# ai_breakout_rpibplus.net
KiCad netlist of a schematic drawn in EAGLE
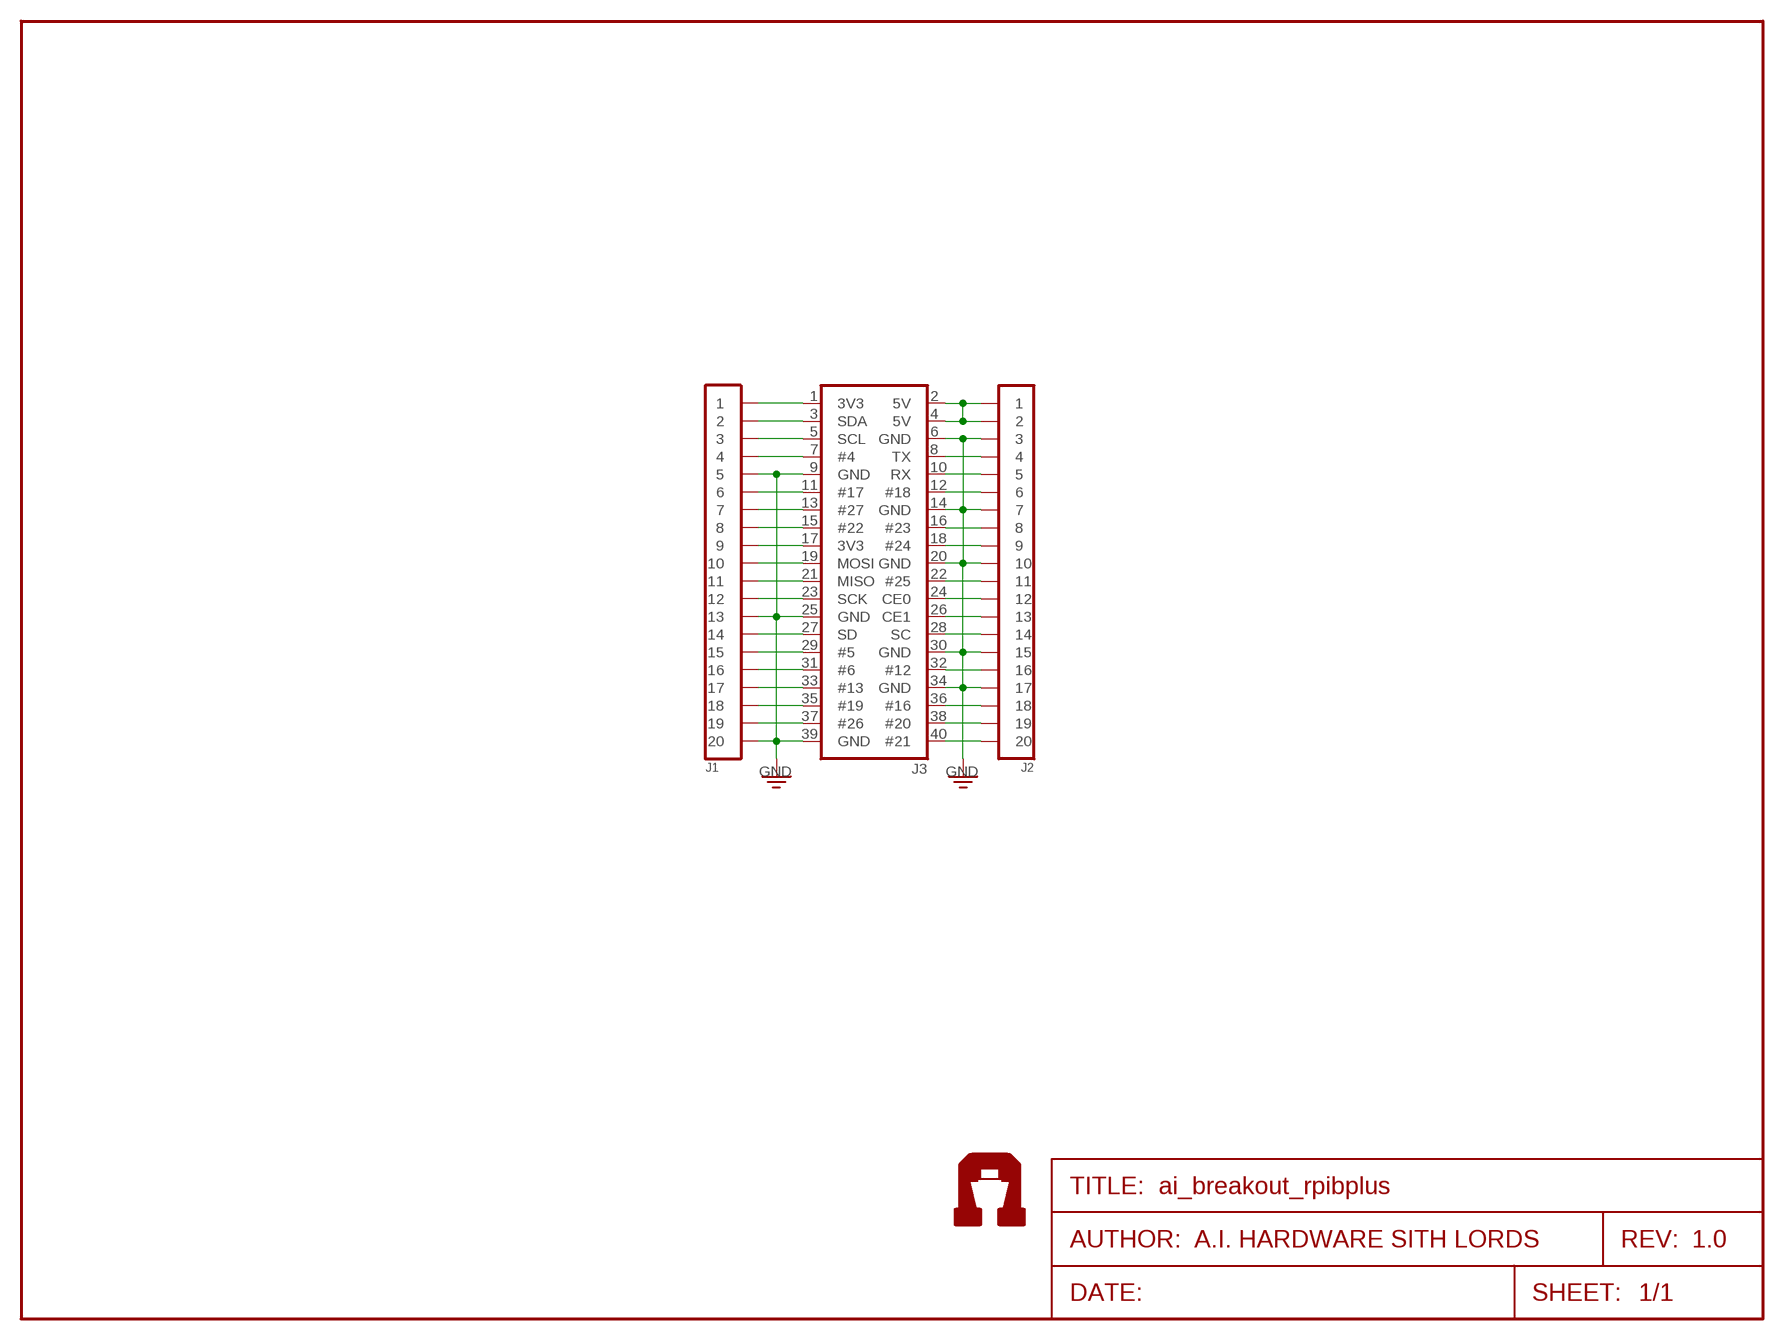
[diagram p0: schematic, sheet 1]

(export (version "E")
  (design (tool "Eeschema 10.0.6"))
  (components
    (comp (ref "J1")
      (value "1X20")
      (footprint "eagle-import:1X20")
      (libsource (lib "eagle-import") (part "1X20"))
    )
    (comp (ref "J2")
      (value "1X20NOFIRST")
      (footprint "eagle-import:1X20-NOFIRST")
      (libsource (lib "eagle-import") (part "1X20NOFIRST"))
    )
    (comp (ref "J3")
      (value "2X20-RPI-BRK")
      (footprint "eagle-import:2X20-RPI-BRK")
      (libsource (lib "eagle-import") (part "2X20-RPI-BRK"))
    )
    (comp (ref "U$1")
      (value "AI-LOGOXS")
      (footprint "eagle-import:AI-LOGO-XS")
      (libsource (lib "eagle-import") (part "AI-LOGOXS"))
    )
    (comp (ref "U$2")
      (value "AI-LOGOXS")
      (footprint "eagle-import:AI-LOGO-XS")
      (libsource (lib "eagle-import") (part "AI-LOGOXS"))
    )
  )
  (nets
    (net (code "1") (name "GND") (class "Default")
      (node (ref "J1") (pin "13") (pinfunction "13_13") (pintype "bidirectional"))
      (node (ref "J1") (pin "20") (pinfunction "20_20") (pintype "bidirectional"))
      (node (ref "J1") (pin "5") (pinfunction "5_5") (pintype "bidirectional"))
      (node (ref "J2") (pin "10") (pinfunction "10_10") (pintype "bidirectional"))
      (node (ref "J2") (pin "15") (pinfunction "15_15") (pintype "bidirectional"))
      (node (ref "J2") (pin "17") (pinfunction "17_17") (pintype "bidirectional"))
      (node (ref "J2") (pin "3") (pinfunction "3_3") (pintype "bidirectional"))
      (node (ref "J2") (pin "7") (pinfunction "7_7") (pintype "bidirectional"))
      (node (ref "J3") (pin "14") (pinfunction "GND_14") (pintype "bidirectional"))
      (node (ref "J3") (pin "20") (pinfunction "GND_20") (pintype "bidirectional"))
      (node (ref "J3") (pin "25") (pinfunction "GND_25") (pintype "bidirectional"))
      (node (ref "J3") (pin "30") (pinfunction "GND_30") (pintype "bidirectional"))
      (node (ref "J3") (pin "34") (pinfunction "GND_34") (pintype "bidirectional"))
      (node (ref "J3") (pin "39") (pinfunction "GND_39") (pintype "bidirectional"))
      (node (ref "J3") (pin "6") (pinfunction "GND_6") (pintype "bidirectional"))
      (node (ref "J3") (pin "9") (pinfunction "GND_9") (pintype "bidirectional"))
    )
    (net (code "2") (name "Net-(J1-Pad1)") (class "Default")
      (node (ref "J1") (pin "1") (pinfunction "1_1") (pintype "bidirectional"))
      (node (ref "J3") (pin "1") (pinfunction "3V3_1") (pintype "bidirectional"))
    )
    (net (code "3") (name "Net-(J1-Pad9)") (class "Default")
      (node (ref "J1") (pin "9") (pinfunction "9_9") (pintype "bidirectional"))
      (node (ref "J3") (pin "17") (pinfunction "3V3_17") (pintype "bidirectional"))
    )
    (net (code "4") (name "Net-(J2-Pad1)") (class "Default")
      (node (ref "J2") (pin "1") (pinfunction "1_1") (pintype "bidirectional"))
      (node (ref "J2") (pin "2") (pinfunction "2_2") (pintype "bidirectional"))
      (node (ref "J3") (pin "2") (pinfunction "5V_2") (pintype "bidirectional"))
      (node (ref "J3") (pin "4") (pinfunction "5V_4") (pintype "bidirectional"))
    )
    (net (code "5") (name "Net-(J3-#4)") (class "Default")
      (node (ref "J1") (pin "4") (pinfunction "4_4") (pintype "bidirectional"))
      (node (ref "J3") (pin "7") (pinfunction "#4_7") (pintype "bidirectional"))
    )
    (net (code "6") (name "Net-(J3-#5)") (class "Default")
      (node (ref "J1") (pin "15") (pinfunction "15_15") (pintype "bidirectional"))
      (node (ref "J3") (pin "29") (pinfunction "#5_29") (pintype "bidirectional"))
    )
    (net (code "7") (name "Net-(J3-#6)") (class "Default")
      (node (ref "J1") (pin "16") (pinfunction "16_16") (pintype "bidirectional"))
      (node (ref "J3") (pin "31") (pinfunction "#6_31") (pintype "bidirectional"))
    )
    (net (code "8") (name "Net-(J3-#12)") (class "Default")
      (node (ref "J2") (pin "16") (pinfunction "16_16") (pintype "bidirectional"))
      (node (ref "J3") (pin "32") (pinfunction "#12_32") (pintype "bidirectional"))
    )
    (net (code "9") (name "Net-(J3-#13)") (class "Default")
      (node (ref "J1") (pin "17") (pinfunction "17_17") (pintype "bidirectional"))
      (node (ref "J3") (pin "33") (pinfunction "#13_33") (pintype "bidirectional"))
    )
    (net (code "10") (name "Net-(J3-#16)") (class "Default")
      (node (ref "J2") (pin "18") (pinfunction "18_18") (pintype "bidirectional"))
      (node (ref "J3") (pin "36") (pinfunction "#16_36") (pintype "bidirectional"))
    )
    (net (code "11") (name "Net-(J3-#17)") (class "Default")
      (node (ref "J1") (pin "6") (pinfunction "6_6") (pintype "bidirectional"))
      (node (ref "J3") (pin "11") (pinfunction "#17_11") (pintype "bidirectional"))
    )
    (net (code "12") (name "Net-(J3-#18)") (class "Default")
      (node (ref "J2") (pin "6") (pinfunction "6_6") (pintype "bidirectional"))
      (node (ref "J3") (pin "12") (pinfunction "#18_12") (pintype "bidirectional"))
    )
    (net (code "13") (name "Net-(J3-#19)") (class "Default")
      (node (ref "J1") (pin "18") (pinfunction "18_18") (pintype "bidirectional"))
      (node (ref "J3") (pin "35") (pinfunction "#19_35") (pintype "bidirectional"))
    )
    (net (code "14") (name "Net-(J3-#20)") (class "Default")
      (node (ref "J2") (pin "19") (pinfunction "19_19") (pintype "bidirectional"))
      (node (ref "J3") (pin "38") (pinfunction "#20_38") (pintype "bidirectional"))
    )
    (net (code "15") (name "Net-(J3-#21)") (class "Default")
      (node (ref "J2") (pin "20") (pinfunction "20_20") (pintype "bidirectional"))
      (node (ref "J3") (pin "40") (pinfunction "#21_40") (pintype "bidirectional"))
    )
    (net (code "16") (name "Net-(J3-#22)") (class "Default")
      (node (ref "J1") (pin "8") (pinfunction "8_8") (pintype "bidirectional"))
      (node (ref "J3") (pin "15") (pinfunction "#22_15") (pintype "bidirectional"))
    )
    (net (code "17") (name "Net-(J3-#23)") (class "Default")
      (node (ref "J2") (pin "8") (pinfunction "8_8") (pintype "bidirectional"))
      (node (ref "J3") (pin "16") (pinfunction "#23_16") (pintype "bidirectional"))
    )
    (net (code "18") (name "Net-(J3-#24)") (class "Default")
      (node (ref "J2") (pin "9") (pinfunction "9_9") (pintype "bidirectional"))
      (node (ref "J3") (pin "18") (pinfunction "#24_18") (pintype "bidirectional"))
    )
    (net (code "19") (name "Net-(J3-#25)") (class "Default")
      (node (ref "J2") (pin "11") (pinfunction "11_11") (pintype "bidirectional"))
      (node (ref "J3") (pin "22") (pinfunction "#25_22") (pintype "bidirectional"))
    )
    (net (code "20") (name "Net-(J3-#26)") (class "Default")
      (node (ref "J1") (pin "19") (pinfunction "19_19") (pintype "bidirectional"))
      (node (ref "J3") (pin "37") (pinfunction "#26_37") (pintype "bidirectional"))
    )
    (net (code "21") (name "Net-(J3-#27)") (class "Default")
      (node (ref "J1") (pin "7") (pinfunction "7_7") (pintype "bidirectional"))
      (node (ref "J3") (pin "13") (pinfunction "#27_13") (pintype "bidirectional"))
    )
    (net (code "22") (name "Net-(J3-CE0)") (class "Default")
      (node (ref "J2") (pin "12") (pinfunction "12_12") (pintype "bidirectional"))
      (node (ref "J3") (pin "24") (pinfunction "CE0_24") (pintype "bidirectional"))
    )
    (net (code "23") (name "Net-(J3-CE1)") (class "Default")
      (node (ref "J2") (pin "13") (pinfunction "13_13") (pintype "bidirectional"))
      (node (ref "J3") (pin "26") (pinfunction "CE1_26") (pintype "bidirectional"))
    )
    (net (code "24") (name "Net-(J3-MISO)") (class "Default")
      (node (ref "J1") (pin "11") (pinfunction "11_11") (pintype "bidirectional"))
      (node (ref "J3") (pin "21") (pinfunction "MISO_21") (pintype "bidirectional"))
    )
    (net (code "25") (name "Net-(J3-MOSI)") (class "Default")
      (node (ref "J1") (pin "10") (pinfunction "10_10") (pintype "bidirectional"))
      (node (ref "J3") (pin "19") (pinfunction "MOSI_19") (pintype "bidirectional"))
    )
    (net (code "26") (name "Net-(J3-RX)") (class "Default")
      (node (ref "J2") (pin "5") (pinfunction "5_5") (pintype "bidirectional"))
      (node (ref "J3") (pin "10") (pinfunction "RX_10") (pintype "bidirectional"))
    )
    (net (code "27") (name "Net-(J3-SC)") (class "Default")
      (node (ref "J2") (pin "14") (pinfunction "14_14") (pintype "bidirectional"))
      (node (ref "J3") (pin "28") (pinfunction "SC_28") (pintype "bidirectional"))
    )
    (net (code "28") (name "Net-(J3-SCK)") (class "Default")
      (node (ref "J1") (pin "12") (pinfunction "12_12") (pintype "bidirectional"))
      (node (ref "J3") (pin "23") (pinfunction "SCK_23") (pintype "bidirectional"))
    )
    (net (code "29") (name "Net-(J3-SCL)") (class "Default")
      (node (ref "J1") (pin "3") (pinfunction "3_3") (pintype "bidirectional"))
      (node (ref "J3") (pin "5") (pinfunction "SCL_5") (pintype "bidirectional"))
    )
    (net (code "30") (name "Net-(J3-SD)") (class "Default")
      (node (ref "J1") (pin "14") (pinfunction "14_14") (pintype "bidirectional"))
      (node (ref "J3") (pin "27") (pinfunction "SD_27") (pintype "bidirectional"))
    )
    (net (code "31") (name "Net-(J3-SDA)") (class "Default")
      (node (ref "J1") (pin "2") (pinfunction "2_2") (pintype "bidirectional"))
      (node (ref "J3") (pin "3") (pinfunction "SDA_3") (pintype "bidirectional"))
    )
    (net (code "32") (name "Net-(J3-TX)") (class "Default")
      (node (ref "J2") (pin "4") (pinfunction "4_4") (pintype "bidirectional"))
      (node (ref "J3") (pin "8") (pinfunction "TX_8") (pintype "bidirectional"))
    )
  )
)
